# RWM_Filter.net
KiCad netlist of a schematic drawn in Altium Designer
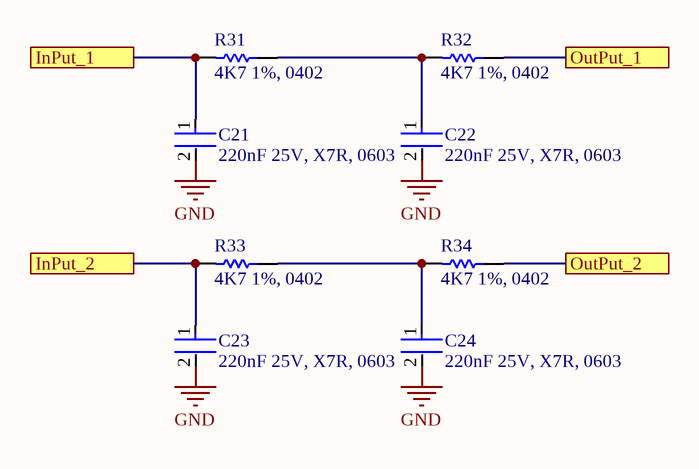
[diagram p0: RWM_Filter.SchDoc]

(export (version "E")
  (design (tool "Eeschema 10.0.6"))
  (components
    (comp (ref "C21")
      (value "220nF 25V, X7R, 0603")
      (footprint "FP-GCM188-0_1-IPC_B")
      (description "Ceramic Capacitor for Automotive 220nF  ±10% 25VDC X7R 0603 Paper T/R")
      (fields (field (name "VOLTAGE") "25V") (field (name "TOLERANCE") "10%"))
      (libsource (lib "Altium Content Vault") (part "02cd4be3c70576c341d710602a673aa"))
    )
    (comp (ref "C22")
      (value "220nF 25V, X7R, 0603")
      (footprint "FP-GCM188-0_1-IPC_B")
      (description "Ceramic Capacitor for Automotive 220nF  ±10% 25VDC X7R 0603 Paper T/R")
      (fields (field (name "VOLTAGE") "25V") (field (name "TOLERANCE") "10%"))
      (libsource (lib "Altium Content Vault") (part "02cd4be3c70576c341d710602a673aa"))
    )
    (comp (ref "C23")
      (value "220nF 25V, X7R, 0603")
      (footprint "FP-GCM188-0_1-IPC_B")
      (description "Ceramic Capacitor for Automotive 220nF  ±10% 25VDC X7R 0603 Paper T/R")
      (fields (field (name "VOLTAGE") "25V") (field (name "TOLERANCE") "10%"))
      (libsource (lib "Altium Content Vault") (part "02cd4be3c70576c341d710602a673aa"))
    )
    (comp (ref "C24")
      (value "220nF 25V, X7R, 0603")
      (footprint "FP-GCM188-0_1-IPC_B")
      (description "Ceramic Capacitor for Automotive 220nF  ±10% 25VDC X7R 0603 Paper T/R")
      (fields (field (name "VOLTAGE") "25V") (field (name "TOLERANCE") "10%"))
      (libsource (lib "Altium Content Vault") (part "02cd4be3c70576c341d710602a673aa"))
    )
    (comp (ref "R31")
      (value "4K7 1%, 0402")
      (footprint "RESC1005X40X25LL05T05")
      (description "Chip Resistor, 4.7 KOhm, +/- 1%, 0.1 W, -55 to 155 degC, 0402 (1005 Metric), RoHS, Tape and Reel")
      (fields (field (name "TOLERANCE") "1%") (field (name "PARTNUMBER") "ERJ-2RKF4701X"))
      (libsource (lib "Altium Content Vault") (part "RES-2"))
    )
    (comp (ref "R32")
      (value "4K7 1%, 0402")
      (footprint "RESC1005X40X25LL05T05")
      (description "Chip Resistor, 4.7 KOhm, +/- 1%, 0.1 W, -55 to 155 degC, 0402 (1005 Metric), RoHS, Tape and Reel")
      (fields (field (name "TOLERANCE") "1%") (field (name "PARTNUMBER") "ERJ-2RKF4701X"))
      (libsource (lib "Altium Content Vault") (part "RES-2"))
    )
    (comp (ref "R33")
      (value "4K7 1%, 0402")
      (footprint "RESC1005X40X25LL05T05")
      (description "Chip Resistor, 4.7 KOhm, +/- 1%, 0.1 W, -55 to 155 degC, 0402 (1005 Metric), RoHS, Tape and Reel")
      (fields (field (name "TOLERANCE") "1%") (field (name "PARTNUMBER") "ERJ-2RKF4701X"))
      (libsource (lib "Altium Content Vault") (part "RES-2"))
    )
    (comp (ref "R34")
      (value "4K7 1%, 0402")
      (footprint "RESC1005X40X25LL05T05")
      (description "Chip Resistor, 4.7 KOhm, +/- 1%, 0.1 W, -55 to 155 degC, 0402 (1005 Metric), RoHS, Tape and Reel")
      (fields (field (name "TOLERANCE") "1%") (field (name "PARTNUMBER") "ERJ-2RKF4701X"))
      (libsource (lib "Altium Content Vault") (part "RES-2"))
    )
  )
  (nets
    (net (code "1") (name "/InPut_1") (class "Default")
      (node (ref "C21") (pin "1") (pinfunction "1_1") (pintype "passive"))
      (node (ref "R31") (pin "2") (pinfunction "2_2") (pintype "passive"))
    )
    (net (code "2") (name "/InPut_2") (class "Default")
      (node (ref "C23") (pin "1") (pinfunction "1_1") (pintype "passive"))
      (node (ref "R33") (pin "2") (pinfunction "2_2") (pintype "passive"))
    )
    (net (code "3") (name "/OutPut_1") (class "Default")
      (node (ref "R32") (pin "1") (pinfunction "1_1") (pintype "passive"))
    )
    (net (code "4") (name "/OutPut_2") (class "Default")
      (node (ref "R34") (pin "1") (pinfunction "1_1") (pintype "passive"))
    )
    (net (code "5") (name "GND") (class "Default")
      (node (ref "C21") (pin "2") (pinfunction "2_2") (pintype "passive"))
      (node (ref "C22") (pin "2") (pinfunction "2_2") (pintype "passive"))
      (node (ref "C23") (pin "2") (pinfunction "2_2") (pintype "passive"))
      (node (ref "C24") (pin "2") (pinfunction "2_2") (pintype "passive"))
    )
    (net (code "6") (name "Net-(C22-Pad1)") (class "Default")
      (node (ref "C22") (pin "1") (pinfunction "1_1") (pintype "passive"))
      (node (ref "R31") (pin "1") (pinfunction "1_1") (pintype "passive"))
      (node (ref "R32") (pin "2") (pinfunction "2_2") (pintype "passive"))
    )
    (net (code "7") (name "Net-(C24-Pad1)") (class "Default")
      (node (ref "C24") (pin "1") (pinfunction "1_1") (pintype "passive"))
      (node (ref "R33") (pin "1") (pinfunction "1_1") (pintype "passive"))
      (node (ref "R34") (pin "2") (pinfunction "2_2") (pintype "passive"))
    )
  )
)
